# al_DozeDot.net
KiCad netlist of a schematic drawn in EAGLE
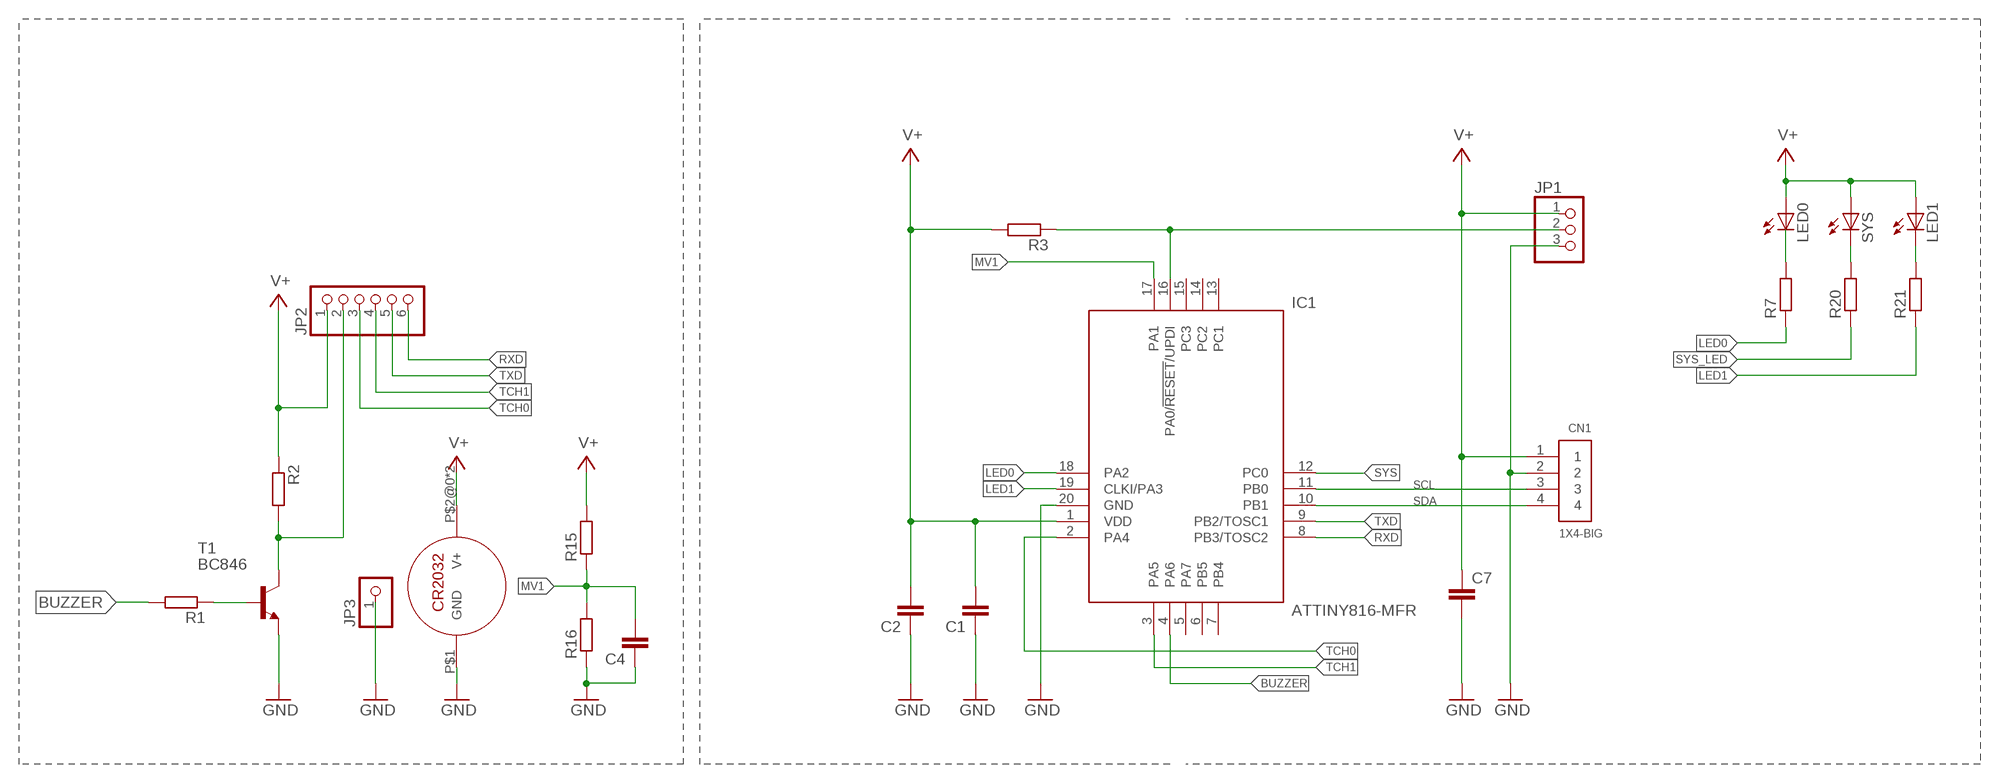
[diagram p0: schematic, sheet 1]

(export (version "E")
  (design (tool "Eeschema 10.0.6"))
  (components
    (comp (ref "C1")
      (value "C-EUC0603")
      (footprint "eagle-import:C0603")
      (libsource (lib "eagle-import") (part "resistor_C-EUC0603"))
    )
    (comp (ref "C2")
      (value "C-EUC0603")
      (footprint "eagle-import:C0603")
      (libsource (lib "eagle-import") (part "resistor_C-EUC0603"))
    )
    (comp (ref "C4")
      (value "C-EUC0603")
      (footprint "eagle-import:C0603")
      (libsource (lib "eagle-import") (part "resistor_C-EUC0603"))
    )
    (comp (ref "C7")
      (value "C-EUC0603K")
      (footprint "eagle-import:C0603K")
      (libsource (lib "eagle-import") (part "C-EUC0603K"))
    )
    (comp (ref "CN1")
      (value "1X4-BIG")
      (footprint "eagle-import:1X04-BIG")
      (libsource (lib "eagle-import") (part "1X4-BIG"))
    )
    (comp (ref "IC1")
      (value "ATTINY816-MFR")
      (footprint "eagle-import:SOIC127P1030X265-20N")
      (libsource (lib "eagle-import") (part "ATTINY816-MFR"))
    )
    (comp (ref "JP1")
      (value "PINHD-1X3")
      (footprint "eagle-import:1X03")
      (libsource (lib "eagle-import") (part "PINHD-1X3"))
    )
    (comp (ref "JP2")
      (value "PINHD-1X6")
      (footprint "eagle-import:1X06")
      (libsource (lib "eagle-import") (part "PINHD-1X6"))
    )
    (comp (ref "JP3")
      (value "PINHD-1X1")
      (footprint "eagle-import:1X01")
      (libsource (lib "eagle-import") (part "PINHD-1X1"))
    )
    (comp (ref "LED0")
      (value "LED_ESML0603")
      (footprint "eagle-import:LED_SML0603")
      (libsource (lib "eagle-import") (part "LED_ESML0603"))
    )
    (comp (ref "LED1")
      (value "LED_ESML0603")
      (footprint "eagle-import:LED_SML0603")
      (libsource (lib "eagle-import") (part "LED_ESML0603"))
    )
    (comp (ref "R1")
      (value "RR0603")
      (footprint "eagle-import:R0603")
      (libsource (lib "eagle-import") (part "RR0603"))
    )
    (comp (ref "R2")
      (value "RR0603")
      (footprint "eagle-import:R0603")
      (libsource (lib "eagle-import") (part "RR0603"))
    )
    (comp (ref "R3")
      (value "R-EU_R0603")
      (footprint "eagle-import:R0603")
      (libsource (lib "eagle-import") (part "R-EU_R0603"))
    )
    (comp (ref "R7")
      (value "R-EU_R0603")
      (footprint "eagle-import:R0603")
      (libsource (lib "eagle-import") (part "R-EU_R0603"))
    )
    (comp (ref "R15")
      (value "R-EU_R0603")
      (footprint "eagle-import:R0603")
      (libsource (lib "eagle-import") (part "R-EU_R0603"))
    )
    (comp (ref "R16")
      (value "R-EU_R0603")
      (footprint "eagle-import:R0603")
      (libsource (lib "eagle-import") (part "R-EU_R0603"))
    )
    (comp (ref "R20")
      (value "R-EU_R0603")
      (footprint "eagle-import:R0603")
      (libsource (lib "eagle-import") (part "R-EU_R0603"))
    )
    (comp (ref "R21")
      (value "R-EU_R0603")
      (footprint "eagle-import:R0603")
      (libsource (lib "eagle-import") (part "R-EU_R0603"))
    )
    (comp (ref "SYS")
      (value "LED_ESML0603")
      (footprint "eagle-import:LED_SML0603")
      (libsource (lib "eagle-import") (part "LED_ESML0603"))
    )
    (comp (ref "T1")
      (value "BC846")
      (footprint "eagle-import:SOT23")
      (libsource (lib "eagle-import") (part "BC846"))
    )
    (comp (ref "U$2")
      (value "CR2032")
      (footprint "eagle-import:DS1092-07-W6L")
      (libsource (lib "eagle-import") (part "CR2032"))
    )
  )
  (nets
    (net (code "1") (name "/SCL") (class "Default")
      (node (ref "CN1") (pin "3") (pinfunction "3_3") (pintype "bidirectional"))
      (node (ref "IC1") (pin "11") (pinfunction "PB0_11") (pintype "passive"))
    )
    (net (code "2") (name "/SDA") (class "Default")
      (node (ref "CN1") (pin "4") (pinfunction "4_4") (pintype "bidirectional"))
      (node (ref "IC1") (pin "10") (pinfunction "PB1_10") (pintype "passive"))
    )
    (net (code "3") (name "BUZZER") (class "Default")
      (node (ref "IC1") (pin "4") (pinfunction "PA6_4") (pintype "passive"))
      (node (ref "R1") (pin "2") (pinfunction "2_2") (pintype "passive"))
    )
    (net (code "4") (name "GND") (class "Default")
      (node (ref "C1") (pin "1") (pinfunction "1_1") (pintype "passive"))
      (node (ref "C2") (pin "1") (pinfunction "1_1") (pintype "passive"))
      (node (ref "C4") (pin "1") (pinfunction "1_1") (pintype "passive"))
      (node (ref "C7") (pin "2") (pinfunction "2_2") (pintype "passive"))
      (node (ref "CN1") (pin "2") (pinfunction "2_2") (pintype "bidirectional"))
      (node (ref "IC1") (pin "20") (pinfunction "GND_20") (pintype "passive"))
      (node (ref "JP1") (pin "3") (pinfunction "3_3") (pintype "passive"))
      (node (ref "JP3") (pin "1") (pinfunction "1_1") (pintype "passive"))
      (node (ref "R16") (pin "1") (pinfunction "1_1") (pintype "passive"))
      (node (ref "T1") (pin "2") (pinfunction "E_2") (pintype "passive"))
      (node (ref "U$2") (pin "P$1") (pinfunction "GND_P$1") (pintype "bidirectional"))
    )
    (net (code "5") (name "LED0") (class "Default")
      (node (ref "IC1") (pin "18") (pinfunction "PA2_18") (pintype "passive"))
      (node (ref "R7") (pin "1") (pinfunction "1_1") (pintype "passive"))
    )
    (net (code "6") (name "LED1") (class "Default")
      (node (ref "IC1") (pin "19") (pinfunction "CLKI/PA3_19") (pintype "passive"))
      (node (ref "R21") (pin "1") (pinfunction "1_1") (pintype "passive"))
    )
    (net (code "7") (name "MV1") (class "Default")
      (node (ref "C4") (pin "2") (pinfunction "2_2") (pintype "passive"))
      (node (ref "IC1") (pin "17") (pinfunction "PA1_17") (pintype "passive"))
      (node (ref "R15") (pin "1") (pinfunction "1_1") (pintype "passive"))
      (node (ref "R16") (pin "2") (pinfunction "2_2") (pintype "passive"))
    )
    (net (code "8") (name "Net-(IC1-PA0{slash}~{RESET}{slash}UPDI)") (class "Default")
      (node (ref "IC1") (pin "16") (pinfunction "PA0/~{RESET}/UPDI_16") (pintype "passive"))
      (node (ref "JP1") (pin "2") (pinfunction "2_2") (pintype "passive"))
      (node (ref "R3") (pin "1") (pinfunction "1_1") (pintype "passive"))
    )
    (net (code "9") (name "Net-(LED0-PadC)") (class "Default")
      (node (ref "LED0") (pin "C") (pinfunction "C_C") (pintype "passive"))
      (node (ref "R7") (pin "2") (pinfunction "2_2") (pintype "passive"))
    )
    (net (code "10") (name "Net-(LED1-PadC)") (class "Default")
      (node (ref "LED1") (pin "C") (pinfunction "C_C") (pintype "passive"))
      (node (ref "R21") (pin "2") (pinfunction "2_2") (pintype "passive"))
    )
    (net (code "11") (name "Net-(R20-Pad2)") (class "Default")
      (node (ref "R20") (pin "2") (pinfunction "2_2") (pintype "passive"))
      (node (ref "SYS") (pin "C") (pinfunction "C_C") (pintype "passive"))
    )
    (net (code "12") (name "Net-(T1-B)") (class "Default")
      (node (ref "R1") (pin "1") (pinfunction "1_1") (pintype "passive"))
      (node (ref "T1") (pin "1") (pinfunction "B_1") (pintype "passive"))
    )
    (net (code "13") (name "Net-(T1-C)") (class "Default")
      (node (ref "JP2") (pin "2") (pinfunction "2_2") (pintype "passive"))
      (node (ref "R2") (pin "2") (pinfunction "2_2") (pintype "passive"))
      (node (ref "T1") (pin "3") (pinfunction "C_3") (pintype "passive"))
    )
    (net (code "14") (name "RXD") (class "Default")
      (node (ref "IC1") (pin "8") (pinfunction "PB3/TOSC2_8") (pintype "passive"))
      (node (ref "JP2") (pin "6") (pinfunction "6_6") (pintype "passive"))
    )
    (net (code "15") (name "SYS") (class "Default")
      (node (ref "IC1") (pin "12") (pinfunction "PC0_12") (pintype "passive"))
    )
    (net (code "16") (name "SYS_LED") (class "Default")
      (node (ref "R20") (pin "1") (pinfunction "1_1") (pintype "passive"))
    )
    (net (code "17") (name "TCH0") (class "Default")
      (node (ref "IC1") (pin "2") (pinfunction "PA4_2") (pintype "passive"))
      (node (ref "JP2") (pin "3") (pinfunction "3_3") (pintype "passive"))
    )
    (net (code "18") (name "TCH1") (class "Default")
      (node (ref "IC1") (pin "3") (pinfunction "PA5_3") (pintype "passive"))
      (node (ref "JP2") (pin "4") (pinfunction "4_4") (pintype "passive"))
    )
    (net (code "19") (name "TXD") (class "Default")
      (node (ref "IC1") (pin "9") (pinfunction "PB2/TOSC1_9") (pintype "passive"))
      (node (ref "JP2") (pin "5") (pinfunction "5_5") (pintype "passive"))
    )
    (net (code "20") (name "V+") (class "Default")
      (node (ref "C1") (pin "2") (pinfunction "2_2") (pintype "passive"))
      (node (ref "C2") (pin "2") (pinfunction "2_2") (pintype "passive"))
      (node (ref "C7") (pin "1") (pinfunction "1_1") (pintype "passive"))
      (node (ref "CN1") (pin "1") (pinfunction "1_1") (pintype "bidirectional"))
      (node (ref "IC1") (pin "1") (pinfunction "VDD_1") (pintype "passive"))
      (node (ref "JP1") (pin "1") (pinfunction "1_1") (pintype "passive"))
      (node (ref "JP2") (pin "1") (pinfunction "1_1") (pintype "passive"))
      (node (ref "LED0") (pin "A") (pinfunction "A_A") (pintype "passive"))
      (node (ref "LED1") (pin "A") (pinfunction "A_A") (pintype "passive"))
      (node (ref "R15") (pin "2") (pinfunction "2_2") (pintype "passive"))
      (node (ref "R2") (pin "1") (pinfunction "1_1") (pintype "passive"))
      (node (ref "R3") (pin "2") (pinfunction "2_2") (pintype "passive"))
      (node (ref "SYS") (pin "A") (pinfunction "A_A") (pintype "passive"))
      (node (ref "U$2") (pin "P$2@0") (pinfunction "V+_P$2@0") (pintype "bidirectional"))
      (node (ref "U$2") (pin "P$2@1") (pinfunction "V+_P$2@1") (pintype "bidirectional"))
    )
    (net (code "21") (name "unconnected-(IC1-PA7-Pad5)") (class "Default")
      (node (ref "IC1") (pin "5") (pinfunction "PA7_5") (pintype "passive"))
    )
    (net (code "22") (name "unconnected-(IC1-PB4-Pad7)") (class "Default")
      (node (ref "IC1") (pin "7") (pinfunction "PB4_7") (pintype "passive"))
    )
    (net (code "23") (name "unconnected-(IC1-PB5-Pad6)") (class "Default")
      (node (ref "IC1") (pin "6") (pinfunction "PB5_6") (pintype "passive"))
    )
    (net (code "24") (name "unconnected-(IC1-PC1-Pad13)") (class "Default")
      (node (ref "IC1") (pin "13") (pinfunction "PC1_13") (pintype "passive"))
    )
    (net (code "25") (name "unconnected-(IC1-PC2-Pad14)") (class "Default")
      (node (ref "IC1") (pin "14") (pinfunction "PC2_14") (pintype "passive"))
    )
    (net (code "26") (name "unconnected-(IC1-PC3-Pad15)") (class "Default")
      (node (ref "IC1") (pin "15") (pinfunction "PC3_15") (pintype "passive"))
    )
  )
)
